# SpockVoice.net
KiCad netlist of a schematic drawn in EAGLE
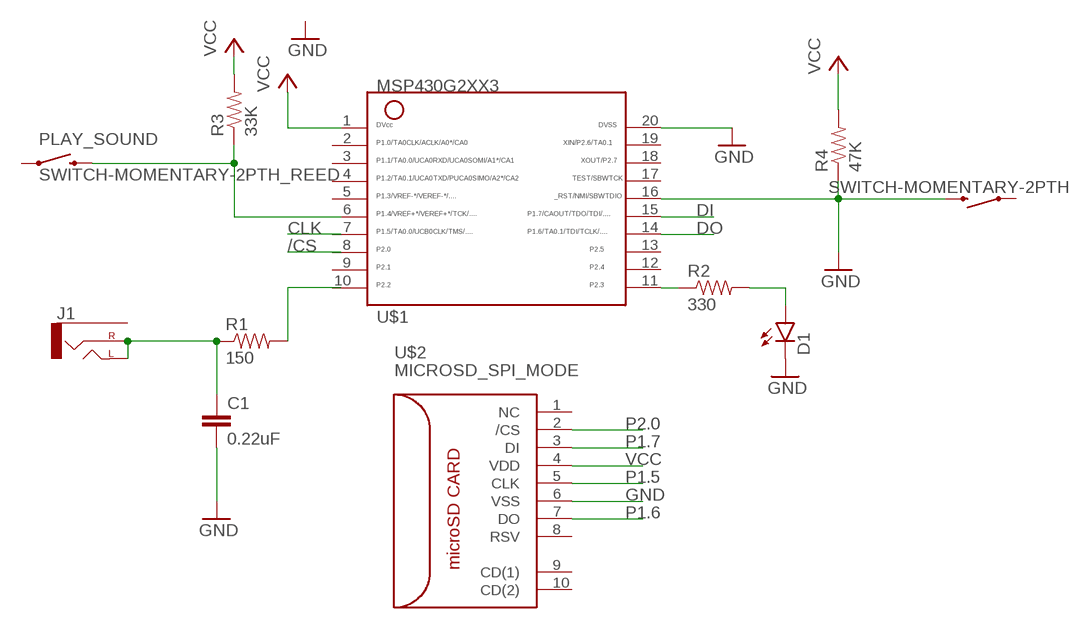
[diagram p0: schematic, sheet 1]

(export (version "E")
  (design (tool "Eeschema 10.0.6"))
  (components
    (comp (ref "C1")
      (value "0.22uF")
      (footprint "eagle-import:0603-CAP")
      (libsource (lib "eagle-import") (part "0.22UF-25V-10%(0603)"))
    )
    (comp (ref "D1")
      (value "LED5MM")
      (footprint "eagle-import:LED5MM")
      (libsource (lib "eagle-import") (part "LED5MM"))
    )
    (comp (ref "J1")
      (value "AUDIO-JACK2.5MM")
      (footprint "eagle-import:STEREOJACK2.5MM_STEREOJACK2.5MM")
      (libsource (lib "eagle-import") (part "AUDIO-JACK2.5MM"))
    )
    (comp (ref "PLAY_SOUND")
      (value "SWITCH-MOMENTARY-2PTH_REED")
      (footprint "eagle-import:REED_SWITCH_PTH")
      (libsource (lib "eagle-import") (part "SWITCH-MOMENTARY-2PTH_REED"))
    )
    (comp (ref "R1")
      (value "150")
      (footprint "eagle-import:AXIAL-0.5")
      (libsource (lib "eagle-import") (part "RESISTORPTH-1/2W"))
    )
    (comp (ref "R2")
      (value "330")
      (footprint "eagle-import:AXIAL-0.5")
      (libsource (lib "eagle-import") (part "RESISTORPTH-1/2W"))
    )
    (comp (ref "R3")
      (value "33K")
      (footprint "eagle-import:AXIAL-0.5")
      (libsource (lib "eagle-import") (part "RESISTORPTH-1/2W"))
    )
    (comp (ref "R4")
      (value "47K")
      (footprint "eagle-import:AXIAL-0.5")
      (libsource (lib "eagle-import") (part "RESISTORPTH-1/2W"))
    )
    (comp (ref "RESET")
      (value "SWITCH-MOMENTARY-2PTH")
      (footprint "eagle-import:TACTILE-PTH")
      (libsource (lib "eagle-import") (part "SWITCH-MOMENTARY-2PTH"))
    )
    (comp (ref "U$1")
      (value "G2XX3---PW20")
      (footprint "eagle-import:PW20")
      (libsource (lib "eagle-import") (part "G2XX3---PW20"))
    )
    (comp (ref "U$2")
      (value "MICROSD_SPI_MODE")
      (footprint "eagle-import:MICRO_SD_CONNECTOR")
      (libsource (lib "eagle-import") (part "MICROSD_SPI_MODE"))
    )
  )
  (nets
    (net (code "2") (name "/DI") (class "Default")
      (node (ref "U$1") (pin "15") (pinfunction "15_15") (pintype "bidirectional"))
    )
    (net (code "3") (name "/DO") (class "Default")
      (node (ref "U$1") (pin "14") (pinfunction "14_14") (pintype "bidirectional"))
    )
    (net (code "4") (name "/P1.5") (class "Default")
      (node (ref "U$2") (pin "5") (pinfunction "CLK_5") (pintype "bidirectional"))
    )
    (net (code "5") (name "/P1.6") (class "Default")
      (node (ref "U$2") (pin "7") (pinfunction "DO_7") (pintype "bidirectional"))
    )
    (net (code "6") (name "/P1.7") (class "Default")
      (node (ref "U$2") (pin "3") (pinfunction "DI_3") (pintype "bidirectional"))
    )
    (net (code "7") (name "/P2.0") (class "Default")
      (node (ref "U$2") (pin "2") (pinfunction "/CS_2") (pintype "bidirectional"))
    )
    (net (code "9") (name "GND") (class "Default")
      (node (ref "C1") (pin "2") (pinfunction "2_2") (pintype "passive"))
      (node (ref "D1") (pin "K") (pinfunction "C_K") (pintype "passive"))
      (node (ref "R4") (pin "P$1") (pinfunction "1_P$1") (pintype "passive"))
      (node (ref "RESET") (pin "3") (pinfunction "2_3") (pintype "passive"))
      (node (ref "U$1") (pin "16") (pinfunction "16_16") (pintype "bidirectional"))
      (node (ref "U$1") (pin "20") (pinfunction "20_20") (pintype "bidirectional"))
      (node (ref "U$2") (pin "6") (pinfunction "VSS_6") (pintype "bidirectional"))
    )
    (net (code "10") (name "Net-(J1-LEFT)") (class "Default")
      (node (ref "C1") (pin "1") (pinfunction "1_1") (pintype "passive"))
      (node (ref "J1") (pin "SHIELD") (pinfunction "LEFT_SHIELD") (pintype "bidirectional"))
      (node (ref "J1") (pin "TIP") (pinfunction "RIGHT_TIP") (pintype "bidirectional"))
      (node (ref "R1") (pin "P$1") (pinfunction "1_P$1") (pintype "passive"))
    )
    (net (code "11") (name "Net-(PLAY_SOUND-2)") (class "Default")
      (node (ref "PLAY_SOUND") (pin "P$2") (pinfunction "2_P$2") (pintype "passive"))
      (node (ref "R3") (pin "P$1") (pinfunction "1_P$1") (pintype "passive"))
    )
    (net (code "12") (name "Net-(R2-1)") (class "Default")
      (node (ref "R2") (pin "P$1") (pinfunction "1_P$1") (pintype "passive"))
      (node (ref "U$1") (pin "11") (pinfunction "11_11") (pintype "bidirectional"))
    )
    (net (code "13") (name "Net-(R2-2)") (class "Default")
      (node (ref "D1") (pin "A") (pinfunction "A_A") (pintype "passive"))
      (node (ref "R2") (pin "P$2") (pinfunction "2_P$2") (pintype "passive"))
    )
    (net (code "14") (name "VCC") (class "Default")
      (node (ref "R3") (pin "P$2") (pinfunction "2_P$2") (pintype "passive"))
      (node (ref "R4") (pin "P$2") (pinfunction "2_P$2") (pintype "passive"))
      (node (ref "U$2") (pin "4") (pinfunction "VDD_4") (pintype "bidirectional"))
    )
    (net (code "15") (name "unconnected-(J1-SLEEVE-PadRING1)") (class "Default")
      (node (ref "J1") (pin "RING1") (pinfunction "SLEEVE_RING1") (pintype "bidirectional"))
    )
    (net (code "16") (name "unconnected-(PLAY_SOUND-1-PadP$1)") (class "Default")
      (node (ref "PLAY_SOUND") (pin "P$1") (pinfunction "1_P$1") (pintype "passive"))
    )
    (net (code "17") (name "unconnected-(R1-2-PadP$2)") (class "Default")
      (node (ref "R1") (pin "P$2") (pinfunction "2_P$2") (pintype "passive"))
    )
    (net (code "18") (name "unconnected-(RESET-Pad1)") (class "Default")
      (node (ref "RESET") (pin "1") (pinfunction "1_1") (pintype "passive"))
    )
    (net (code "19") (name "unconnected-(U$1-Pad1)") (class "Default")
      (node (ref "U$1") (pin "1") (pinfunction "1_1") (pintype "bidirectional"))
    )
    (net (code "20") (name "unconnected-(U$1-Pad2)") (class "Default")
      (node (ref "U$1") (pin "2") (pinfunction "2_2") (pintype "bidirectional"))
    )
    (net (code "21") (name "unconnected-(U$1-Pad3)") (class "Default")
      (node (ref "U$1") (pin "3") (pinfunction "3_3") (pintype "bidirectional"))
    )
    (net (code "22") (name "unconnected-(U$1-Pad4)") (class "Default")
      (node (ref "U$1") (pin "4") (pinfunction "4_4") (pintype "bidirectional"))
    )
    (net (code "23") (name "unconnected-(U$1-Pad5)") (class "Default")
      (node (ref "U$1") (pin "5") (pinfunction "5_5") (pintype "bidirectional"))
    )
    (net (code "24") (name "unconnected-(U$1-Pad6)") (class "Default")
      (node (ref "U$1") (pin "6") (pinfunction "6_6") (pintype "bidirectional"))
    )
    (net (code "25") (name "unconnected-(U$1-Pad7)") (class "Default")
      (node (ref "U$1") (pin "7") (pinfunction "7_7") (pintype "bidirectional"))
    )
    (net (code "26") (name "unconnected-(U$1-Pad8)") (class "Default")
      (node (ref "U$1") (pin "8") (pinfunction "8_8") (pintype "bidirectional"))
    )
    (net (code "27") (name "unconnected-(U$1-Pad9)") (class "Default")
      (node (ref "U$1") (pin "9") (pinfunction "9_9") (pintype "bidirectional"))
    )
    (net (code "28") (name "unconnected-(U$1-Pad10)") (class "Default")
      (node (ref "U$1") (pin "10") (pinfunction "10_10") (pintype "bidirectional"))
    )
    (net (code "29") (name "unconnected-(U$1-Pad12)") (class "Default")
      (node (ref "U$1") (pin "12") (pinfunction "12_12") (pintype "bidirectional"))
    )
    (net (code "30") (name "unconnected-(U$1-Pad13)") (class "Default")
      (node (ref "U$1") (pin "13") (pinfunction "13_13") (pintype "bidirectional"))
    )
    (net (code "31") (name "unconnected-(U$1-Pad17)") (class "Default")
      (node (ref "U$1") (pin "17") (pinfunction "17_17") (pintype "bidirectional"))
    )
    (net (code "32") (name "unconnected-(U$1-Pad18)") (class "Default")
      (node (ref "U$1") (pin "18") (pinfunction "18_18") (pintype "bidirectional"))
    )
    (net (code "33") (name "unconnected-(U$1-Pad19)") (class "Default")
      (node (ref "U$1") (pin "19") (pinfunction "19_19") (pintype "bidirectional"))
    )
    (net (code "34") (name "unconnected-(U$2-CD(1)-Pad9)") (class "Default")
      (node (ref "U$2") (pin "9") (pinfunction "CD(1)_9") (pintype "bidirectional"))
    )
    (net (code "35") (name "unconnected-(U$2-CD(2)-Pad10)") (class "Default")
      (node (ref "U$2") (pin "10") (pinfunction "CD(2)_10") (pintype "bidirectional"))
    )
    (net (code "36") (name "unconnected-(U$2-NC-Pad1)") (class "Default")
      (node (ref "U$2") (pin "1") (pinfunction "NC_1") (pintype "bidirectional"))
    )
    (net (code "37") (name "unconnected-(U$2-RSV-Pad8)") (class "Default")
      (node (ref "U$2") (pin "8") (pinfunction "RSV_8") (pintype "bidirectional"))
    )
  )
)
